# PCB_PI.net
KiCad netlist of a schematic drawn in EasyEDA
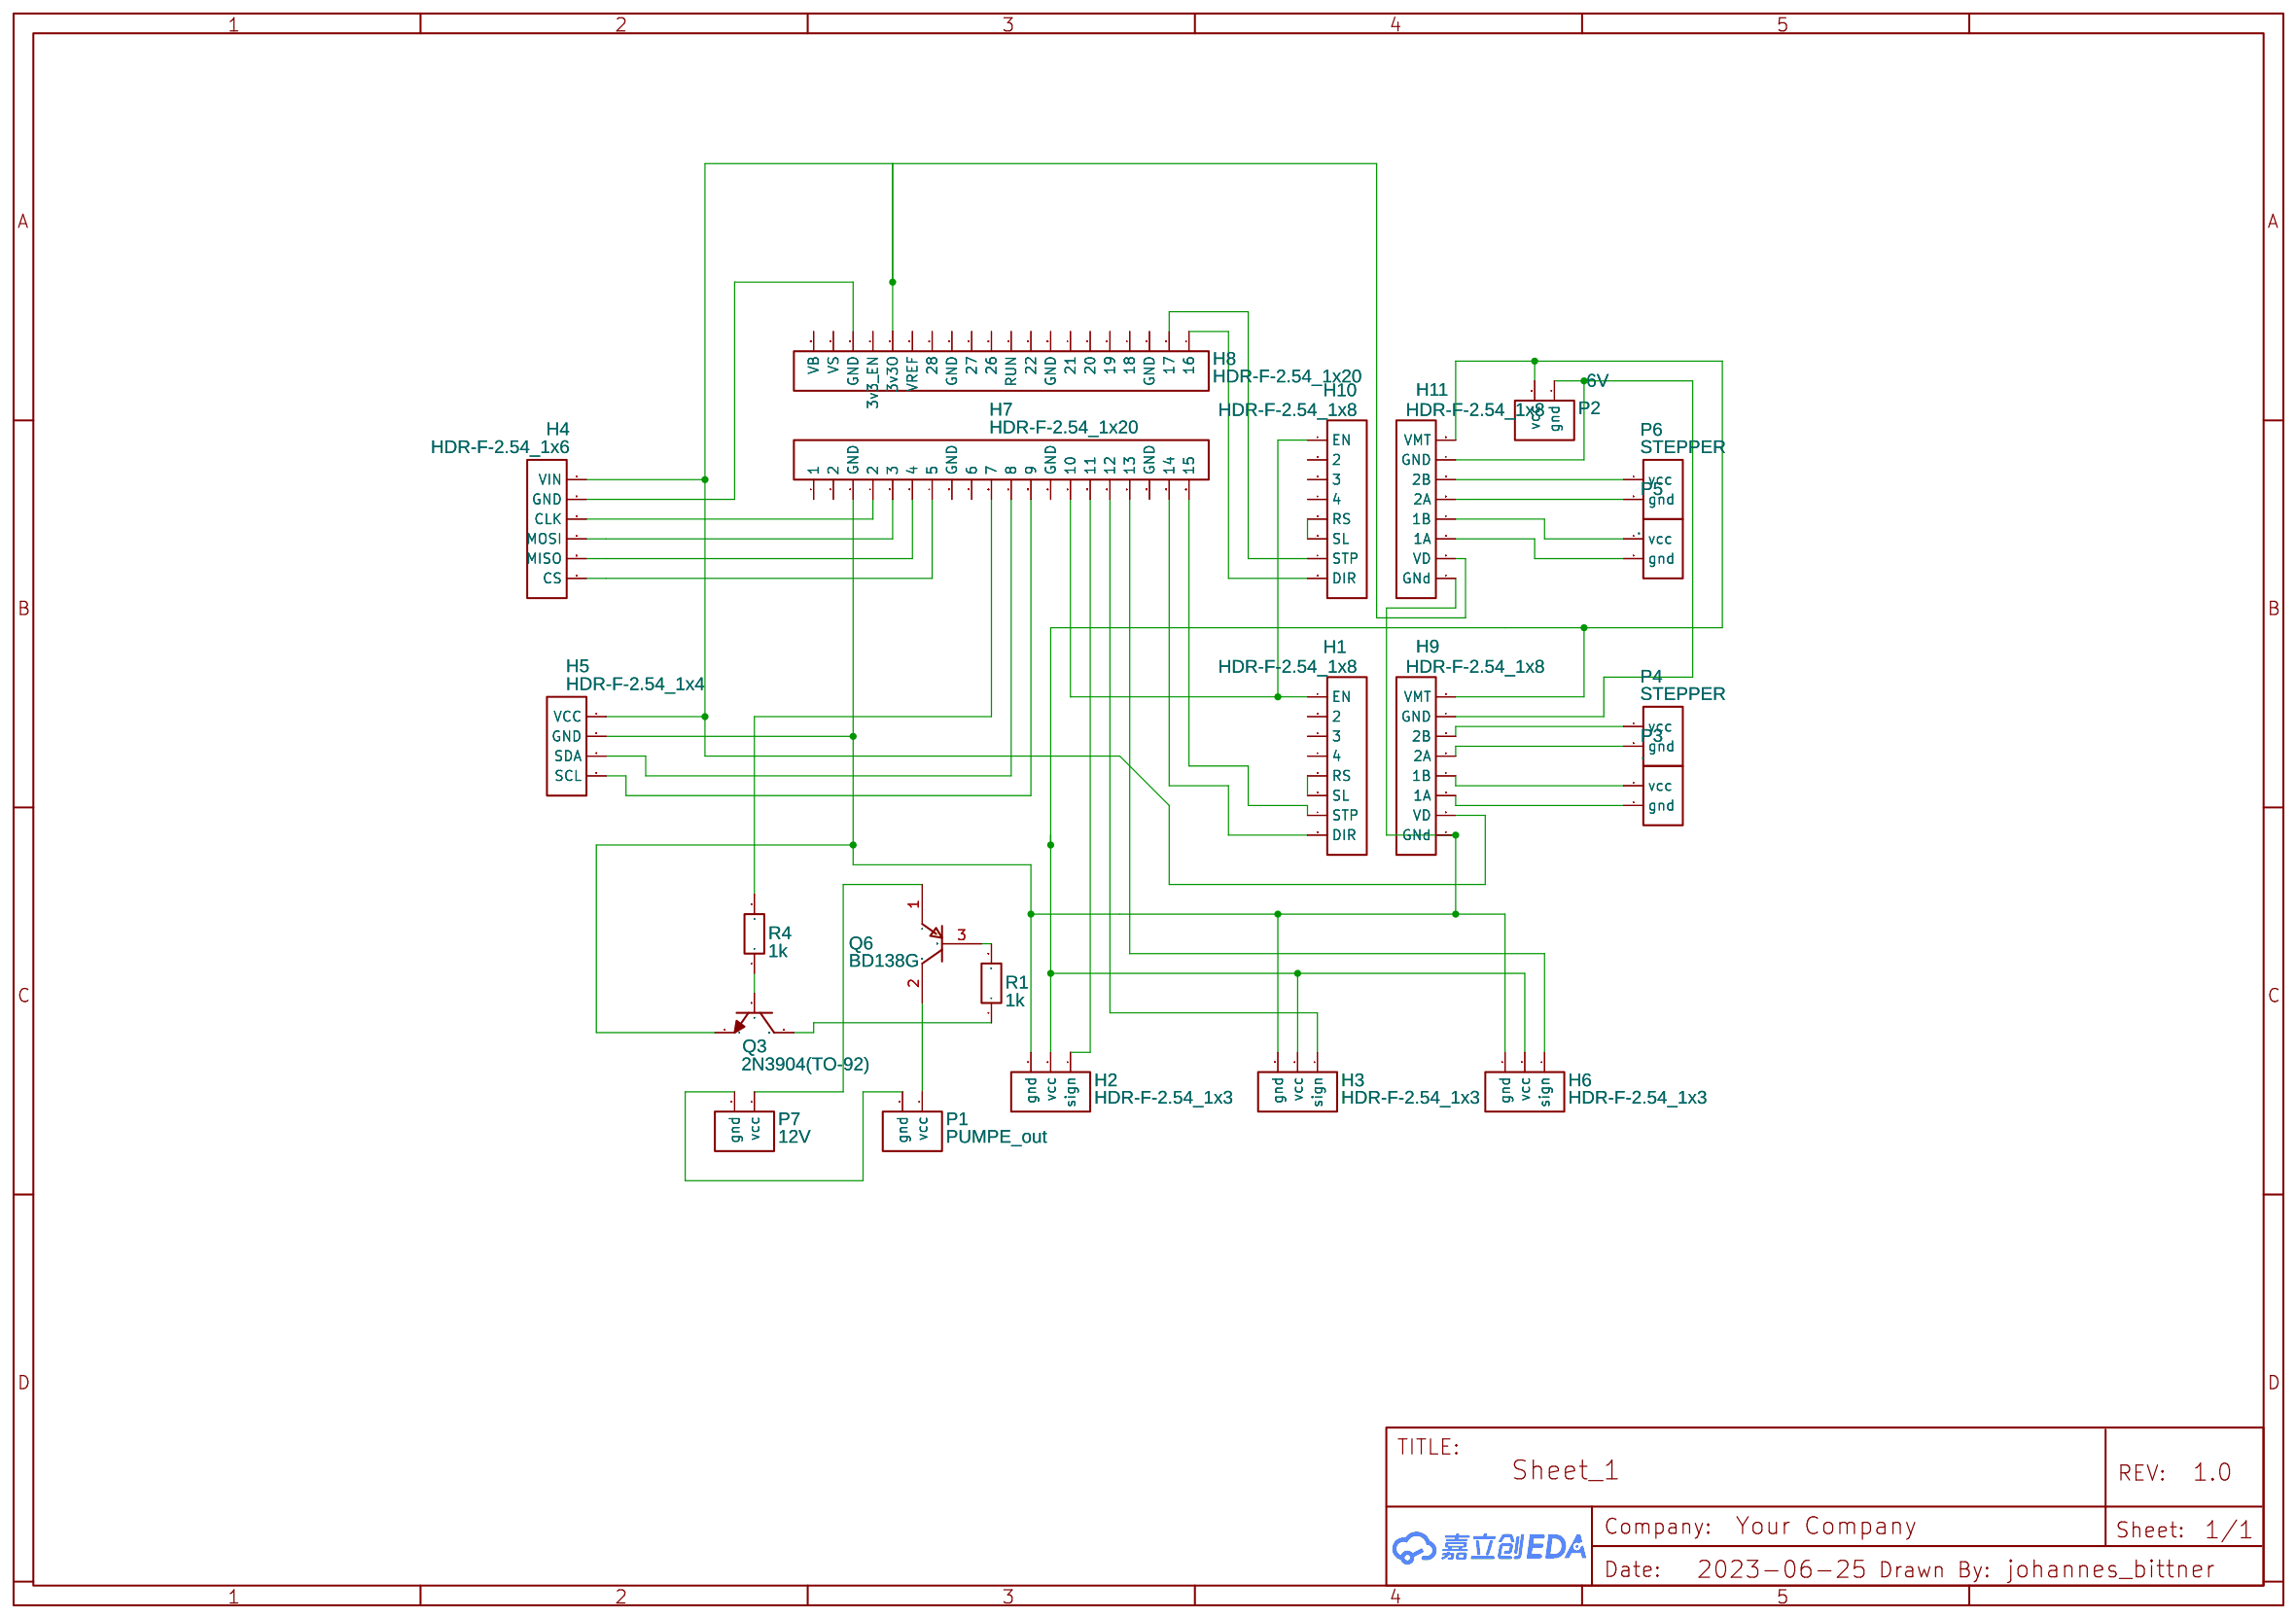
[diagram p0: schematic sheet]

(export (version "E")
  (design (tool "Eeschema 10.0.6"))
  (components
    (comp (ref "H1")
      (value "HDR-F-2.54_1x8")
      (fields (field (name "BOM_Supplier Part") "C225505"))
      (libsource (lib "") (part "HDR-F-2.54_1x8_1"))
    )
    (comp (ref "H2")
      (value "HDR-F-2.54_1x3")
      (fields (field (name "BOM_Supplier Part") "C146690"))
      (libsource (lib "") (part "HDR-F-2.54_1x3"))
    )
    (comp (ref "H3")
      (value "HDR-F-2.54_1x3")
      (fields (field (name "BOM_Supplier Part") "C146690"))
      (libsource (lib "") (part "HDR-F-2.54_1x3"))
    )
    (comp (ref "H4")
      (value "HDR-F-2.54_1x6")
      (fields (field (name "BOM_Supplier Part") "C40877"))
      (libsource (lib "") (part "HDR-F-2.54_1x6"))
    )
    (comp (ref "H5")
      (value "HDR-F-2.54_1x4")
      (fields (field (name "BOM_Supplier Part") "C225501"))
      (libsource (lib "") (part "HDR-F-2.54_1x4"))
    )
    (comp (ref "H6")
      (value "HDR-F-2.54_1x3")
      (fields (field (name "BOM_Supplier Part") "C146690"))
      (libsource (lib "") (part "HDR-F-2.54_1x3"))
    )
    (comp (ref "H7")
      (value "HDR-F-2.54_1x20")
      (fields (field (name "BOM_Supplier Part") "C50984"))
      (libsource (lib "") (part "HDR-F-2.54_1x20"))
    )
    (comp (ref "H8")
      (value "HDR-F-2.54_1x20")
      (fields (field (name "BOM_Supplier Part") "C50984"))
      (libsource (lib "") (part "HDR-F-2.54_1x20_1"))
    )
    (comp (ref "H9")
      (value "HDR-F-2.54_1x8")
      (fields (field (name "BOM_Supplier Part") "C225505"))
      (libsource (lib "") (part "HDR-F-2.54_1x8"))
    )
    (comp (ref "H10")
      (value "HDR-F-2.54_1x8")
      (fields (field (name "BOM_Supplier Part") "C225505"))
      (libsource (lib "") (part "HDR-F-2.54_1x8_1"))
    )
    (comp (ref "H11")
      (value "HDR-F-2.54_1x8")
      (fields (field (name "BOM_Supplier Part") "C225505"))
      (libsource (lib "") (part "HDR-F-2.54_1x8"))
    )
    (comp (ref "P1") (value "PUMPE_out") (libsource (lib "") (part "CONN-TH_2P-P5.00_1")))
    (comp (ref "P2") (value "6V") (libsource (lib "") (part "CONN-TH_2P-P5.00_2")))
    (comp (ref "P3") (value ".") (libsource (lib "") (part "CONN-TH_2P-P5.00")))
    (comp (ref "P4") (value "STEPPER") (libsource (lib "") (part "CONN-TH_2P-P5.00")))
    (comp (ref "P5") (value ".") (libsource (lib "") (part "CONN-TH_2P-P5.00")))
    (comp (ref "P6") (value "STEPPER") (libsource (lib "") (part "CONN-TH_2P-P5.00")))
    (comp (ref "P7") (value "12V") (libsource (lib "") (part "CONN-TH_2P-P5.00_1")))
    (comp (ref "Q3")
      (value "2N3904(TO-92)")
      (fields (field (name "BOM_Manufacturer Part") "2N3904") (field (name "BOM_Supplier Part") "C118538"))
      (libsource (lib "") (part "2N3904(TO-92)"))
    )
    (comp (ref "Q6") (value "BD138G") (libsource (lib "") (part "BD138G")))
    (comp (ref "R1") (value "1k") (libsource (lib "") (part "R_AXIAL-0.5_EU")))
    (comp (ref "R4") (value "1k") (libsource (lib "") (part "R_AXIAL-0.5_EU")))
  )
  (nets
    (net (code "1") (name "Net-(H1-DIR)") (class "Default")
      (node (ref "H1") (pin "8") (pinfunction "DIR_8") (pintype "unspecified"))
      (node (ref "H7") (pin "19") (pinfunction "14_19") (pintype "unspecified"))
    )
    (net (code "2") (name "Net-(H1-EN)") (class "Default")
      (node (ref "H1") (pin "1") (pinfunction "EN_1") (pintype "unspecified"))
      (node (ref "H10") (pin "1") (pinfunction "EN_1") (pintype "unspecified"))
      (node (ref "H7") (pin "14") (pinfunction "10_14") (pintype "unspecified"))
    )
    (net (code "3") (name "Net-(H1-RS)") (class "Default")
      (node (ref "H1") (pin "5") (pinfunction "RS_5") (pintype "unspecified"))
      (node (ref "H1") (pin "6") (pinfunction "SL_6") (pintype "unspecified"))
    )
    (net (code "4") (name "Net-(H1-STP)") (class "Default")
      (node (ref "H1") (pin "7") (pinfunction "STP_7") (pintype "unspecified"))
      (node (ref "H7") (pin "20") (pinfunction "15_20") (pintype "unspecified"))
    )
    (net (code "5") (name "Net-(H2-sign)") (class "Default")
      (node (ref "H2") (pin "1") (pinfunction "sign_1") (pintype "input"))
      (node (ref "H7") (pin "15") (pinfunction "11_15") (pintype "unspecified"))
    )
    (net (code "6") (name "Net-(H3-sign)") (class "Default")
      (node (ref "H3") (pin "1") (pinfunction "sign_1") (pintype "input"))
      (node (ref "H7") (pin "16") (pinfunction "12_16") (pintype "unspecified"))
    )
    (net (code "7") (name "Net-(H4-CLK)") (class "Default")
      (node (ref "H4") (pin "3") (pinfunction "CLK_3") (pintype "input"))
      (node (ref "H7") (pin "4") (pinfunction "2_4") (pintype "unspecified"))
    )
    (net (code "8") (name "Net-(H4-CS)") (class "Default")
      (node (ref "H4") (pin "6") (pinfunction "CS_6") (pintype "input"))
      (node (ref "H7") (pin "7") (pinfunction "5_7") (pintype "unspecified"))
    )
    (net (code "9") (name "Net-(H4-GND)") (class "Default")
      (node (ref "H4") (pin "2") (pinfunction "GND_2") (pintype "input"))
      (node (ref "H8") (pin "18") (pinfunction "GND_18") (pintype "unspecified"))
    )
    (net (code "10") (name "Net-(H4-MISO)") (class "Default")
      (node (ref "H4") (pin "5") (pinfunction "MISO_5") (pintype "input"))
      (node (ref "H7") (pin "6") (pinfunction "4_6") (pintype "unspecified"))
    )
    (net (code "11") (name "Net-(H4-MOSI)") (class "Default")
      (node (ref "H4") (pin "4") (pinfunction "MOSI_4") (pintype "input"))
      (node (ref "H7") (pin "5") (pinfunction "3_5") (pintype "unspecified"))
    )
    (net (code "12") (name "Net-(H5-SCL)") (class "Default")
      (node (ref "H5") (pin "1") (pinfunction "SCL_1") (pintype "unspecified"))
      (node (ref "H7") (pin "12") (pinfunction "9_12") (pintype "unspecified"))
    )
    (net (code "13") (name "Net-(H5-SDA)") (class "Default")
      (node (ref "H5") (pin "2") (pinfunction "SDA_2") (pintype "unspecified"))
      (node (ref "H7") (pin "11") (pinfunction "8_11") (pintype "unspecified"))
    )
    (net (code "14") (name "Net-(H6-sign)") (class "Default")
      (node (ref "H6") (pin "1") (pinfunction "sign_1") (pintype "input"))
      (node (ref "H7") (pin "17") (pinfunction "13_17") (pintype "unspecified"))
    )
    (net (code "15") (name "Net-(H7-7)") (class "Default")
      (node (ref "H7") (pin "10") (pinfunction "7_10") (pintype "unspecified"))
      (node (ref "R4") (pin "2") (pinfunction "2_2") (pintype "unspecified"))
    )
    (net (code "16") (name "Net-(H9-1A)") (class "Default")
      (node (ref "H9") (pin "3") (pinfunction "1A_3") (pintype "unspecified"))
      (node (ref "P3") (pin "2") (pinfunction "gnd_2") (pintype "unspecified"))
    )
    (net (code "17") (name "Net-(H9-1B)") (class "Default")
      (node (ref "H9") (pin "4") (pinfunction "1B_4") (pintype "unspecified"))
      (node (ref "P3") (pin "1") (pinfunction "vcc_1") (pintype "unspecified"))
    )
    (net (code "18") (name "Net-(H9-2A)") (class "Default")
      (node (ref "H9") (pin "5") (pinfunction "2A_5") (pintype "unspecified"))
      (node (ref "P4") (pin "2") (pinfunction "gnd_2") (pintype "unspecified"))
    )
    (net (code "19") (name "Net-(H9-2B)") (class "Default")
      (node (ref "H9") (pin "6") (pinfunction "2B_6") (pintype "unspecified"))
      (node (ref "P4") (pin "1") (pinfunction "vcc_1") (pintype "unspecified"))
    )
    (net (code "20") (name "Net-(H10-DIR)") (class "Default")
      (node (ref "H10") (pin "8") (pinfunction "DIR_8") (pintype "unspecified"))
      (node (ref "H8") (pin "1") (pinfunction "16_1") (pintype "unspecified"))
    )
    (net (code "21") (name "Net-(H10-RS)") (class "Default")
      (node (ref "H10") (pin "5") (pinfunction "RS_5") (pintype "unspecified"))
      (node (ref "H10") (pin "6") (pinfunction "SL_6") (pintype "unspecified"))
    )
    (net (code "22") (name "Net-(H10-STP)") (class "Default")
      (node (ref "H10") (pin "7") (pinfunction "STP_7") (pintype "unspecified"))
      (node (ref "H8") (pin "2") (pinfunction "17_2") (pintype "unspecified"))
    )
    (net (code "23") (name "Net-(H11-1A)") (class "Default")
      (node (ref "H11") (pin "3") (pinfunction "1A_3") (pintype "unspecified"))
      (node (ref "P5") (pin "2") (pinfunction "gnd_2") (pintype "unspecified"))
    )
    (net (code "24") (name "Net-(H11-1B)") (class "Default")
      (node (ref "H11") (pin "4") (pinfunction "1B_4") (pintype "unspecified"))
      (node (ref "P5") (pin "1") (pinfunction "vcc_1") (pintype "unspecified"))
    )
    (net (code "25") (name "Net-(H11-2A)") (class "Default")
      (node (ref "H11") (pin "5") (pinfunction "2A_5") (pintype "unspecified"))
      (node (ref "P6") (pin "2") (pinfunction "gnd_2") (pintype "unspecified"))
    )
    (net (code "26") (name "Net-(H11-2B)") (class "Default")
      (node (ref "H11") (pin "6") (pinfunction "2B_6") (pintype "unspecified"))
      (node (ref "P6") (pin "1") (pinfunction "vcc_1") (pintype "unspecified"))
    )
    (net (code "27") (name "Net-(H11-GND)") (class "Default")
      (node (ref "H11") (pin "7") (pinfunction "GND_7") (pintype "unspecified"))
      (node (ref "H9") (pin "7") (pinfunction "GND_7") (pintype "unspecified"))
      (node (ref "P2") (pin "1") (pinfunction "gnd_1") (pintype "unspecified"))
    )
    (net (code "28") (name "Net-(H11-GNd)") (class "Default")
      (node (ref "H11") (pin "1") (pinfunction "GNd_1") (pintype "unspecified"))
      (node (ref "H2") (pin "3") (pinfunction "gnd_3") (pintype "input"))
      (node (ref "H3") (pin "3") (pinfunction "gnd_3") (pintype "input"))
      (node (ref "H5") (pin "3") (pinfunction "GND_3") (pintype "unspecified"))
      (node (ref "H6") (pin "3") (pinfunction "gnd_3") (pintype "input"))
      (node (ref "H7") (pin "3") (pinfunction "GND_3") (pintype "unspecified"))
      (node (ref "H9") (pin "1") (pinfunction "GNd_1") (pintype "unspecified"))
      (node (ref "Q3") (pin "1") (pinfunction "E_1") (pintype "unspecified"))
    )
    (net (code "29") (name "Net-(H11-VD)") (class "Default")
      (node (ref "H11") (pin "2") (pinfunction "VD_2") (pintype "unspecified"))
      (node (ref "H4") (pin "1") (pinfunction "VIN_1") (pintype "input"))
      (node (ref "H5") (pin "4") (pinfunction "VCC_4") (pintype "unspecified"))
      (node (ref "H8") (pin "16") (pinfunction "3v3O_16") (pintype "unspecified"))
      (node (ref "H9") (pin "2") (pinfunction "VD_2") (pintype "unspecified"))
    )
    (net (code "30") (name "Net-(H11-VMT)") (class "Default")
      (node (ref "H11") (pin "8") (pinfunction "VMT_8") (pintype "unspecified"))
      (node (ref "H2") (pin "2") (pinfunction "vcc_2") (pintype "input"))
      (node (ref "H3") (pin "2") (pinfunction "vcc_2") (pintype "input"))
      (node (ref "H6") (pin "2") (pinfunction "vcc_2") (pintype "input"))
      (node (ref "H9") (pin "8") (pinfunction "VMT_8") (pintype "unspecified"))
      (node (ref "P2") (pin "2") (pinfunction "vcc_2") (pintype "unspecified"))
    )
    (net (code "31") (name "Net-(P1-gnd)") (class "Default")
      (node (ref "P1") (pin "2") (pinfunction "gnd_2") (pintype "unspecified"))
      (node (ref "P7") (pin "2") (pinfunction "gnd_2") (pintype "unspecified"))
    )
    (net (code "32") (name "Net-(P1-vcc)") (class "Default")
      (node (ref "P1") (pin "1") (pinfunction "vcc_1") (pintype "unspecified"))
      (node (ref "Q6") (pin "2") (pinfunction "C_2") (pintype "unspecified"))
    )
    (net (code "33") (name "Net-(P7-vcc)") (class "Default")
      (node (ref "P7") (pin "1") (pinfunction "vcc_1") (pintype "unspecified"))
      (node (ref "Q6") (pin "1") (pinfunction "E_1") (pintype "unspecified"))
    )
    (net (code "34") (name "Net-(Q3-B)") (class "Default")
      (node (ref "Q3") (pin "2") (pinfunction "B_2") (pintype "unspecified"))
      (node (ref "R4") (pin "1") (pinfunction "1_1") (pintype "unspecified"))
    )
    (net (code "35") (name "Net-(Q3-C)") (class "Default")
      (node (ref "Q3") (pin "3") (pinfunction "C_3") (pintype "unspecified"))
      (node (ref "R1") (pin "1") (pinfunction "1_1") (pintype "unspecified"))
    )
    (net (code "36") (name "Net-(Q6-B)") (class "Default")
      (node (ref "Q6") (pin "3") (pinfunction "B_3") (pintype "unspecified"))
      (node (ref "R1") (pin "2") (pinfunction "2_2") (pintype "unspecified"))
    )
    (net (code "37") (name "unconnected-(H1-Pad2)") (class "Default")
      (node (ref "H1") (pin "2") (pinfunction "2_2") (pintype "unspecified"))
    )
    (net (code "38") (name "unconnected-(H1-Pad3)") (class "Default")
      (node (ref "H1") (pin "3") (pinfunction "3_3") (pintype "unspecified"))
    )
    (net (code "39") (name "unconnected-(H1-Pad4)") (class "Default")
      (node (ref "H1") (pin "4") (pinfunction "4_4") (pintype "unspecified"))
    )
    (net (code "40") (name "unconnected-(H7-6-Pad9)") (class "Default")
      (node (ref "H7") (pin "9") (pinfunction "6_9") (pintype "unspecified"))
    )
    (net (code "41") (name "unconnected-(H7-GND-Pad8)") (class "Default")
      (node (ref "H7") (pin "8") (pinfunction "GND_8") (pintype "unspecified"))
    )
    (net (code "42") (name "unconnected-(H7-GND-Pad13)") (class "Default")
      (node (ref "H7") (pin "13") (pinfunction "GND_13") (pintype "unspecified"))
    )
    (net (code "43") (name "unconnected-(H7-GND-Pad18)") (class "Default")
      (node (ref "H7") (pin "18") (pinfunction "GND_18") (pintype "unspecified"))
    )
    (net (code "44") (name "unconnected-(H7-Pad1)") (class "Default")
      (node (ref "H7") (pin "1") (pinfunction "1_1") (pintype "unspecified"))
    )
    (net (code "45") (name "unconnected-(H7-Pad2)") (class "Default")
      (node (ref "H7") (pin "2") (pinfunction "2_2") (pintype "unspecified"))
    )
    (net (code "46") (name "unconnected-(H8-3v3_EN-Pad17)") (class "Default")
      (node (ref "H8") (pin "17") (pinfunction "3v3_EN_17") (pintype "unspecified"))
    )
    (net (code "47") (name "unconnected-(H8-18-Pad4)") (class "Default")
      (node (ref "H8") (pin "4") (pinfunction "18_4") (pintype "unspecified"))
    )
    (net (code "48") (name "unconnected-(H8-19-Pad5)") (class "Default")
      (node (ref "H8") (pin "5") (pinfunction "19_5") (pintype "unspecified"))
    )
    (net (code "49") (name "unconnected-(H8-20-Pad6)") (class "Default")
      (node (ref "H8") (pin "6") (pinfunction "20_6") (pintype "unspecified"))
    )
    (net (code "50") (name "unconnected-(H8-21-Pad7)") (class "Default")
      (node (ref "H8") (pin "7") (pinfunction "21_7") (pintype "unspecified"))
    )
    (net (code "51") (name "unconnected-(H8-22-Pad9)") (class "Default")
      (node (ref "H8") (pin "9") (pinfunction "22_9") (pintype "unspecified"))
    )
    (net (code "52") (name "unconnected-(H8-26-Pad11)") (class "Default")
      (node (ref "H8") (pin "11") (pinfunction "26_11") (pintype "unspecified"))
    )
    (net (code "53") (name "unconnected-(H8-27-Pad12)") (class "Default")
      (node (ref "H8") (pin "12") (pinfunction "27_12") (pintype "unspecified"))
    )
    (net (code "54") (name "unconnected-(H8-28-Pad14)") (class "Default")
      (node (ref "H8") (pin "14") (pinfunction "28_14") (pintype "unspecified"))
    )
    (net (code "55") (name "unconnected-(H8-GND-Pad3)") (class "Default")
      (node (ref "H8") (pin "3") (pinfunction "GND_3") (pintype "unspecified"))
    )
    (net (code "56") (name "unconnected-(H8-GND-Pad8)") (class "Default")
      (node (ref "H8") (pin "8") (pinfunction "GND_8") (pintype "unspecified"))
    )
    (net (code "57") (name "unconnected-(H8-GND-Pad13)") (class "Default")
      (node (ref "H8") (pin "13") (pinfunction "GND_13") (pintype "unspecified"))
    )
    (net (code "58") (name "unconnected-(H8-RUN-Pad10)") (class "Default")
      (node (ref "H8") (pin "10") (pinfunction "RUN_10") (pintype "unspecified"))
    )
    (net (code "59") (name "unconnected-(H8-VB-Pad20)") (class "Default")
      (node (ref "H8") (pin "20") (pinfunction "VB_20") (pintype "unspecified"))
    )
    (net (code "60") (name "unconnected-(H8-VREF-Pad15)") (class "Default")
      (node (ref "H8") (pin "15") (pinfunction "VREF_15") (pintype "unspecified"))
    )
    (net (code "61") (name "unconnected-(H8-VS-Pad19)") (class "Default")
      (node (ref "H8") (pin "19") (pinfunction "VS_19") (pintype "unspecified"))
    )
    (net (code "62") (name "unconnected-(H10-Pad2)") (class "Default")
      (node (ref "H10") (pin "2") (pinfunction "2_2") (pintype "unspecified"))
    )
    (net (code "63") (name "unconnected-(H10-Pad3)") (class "Default")
      (node (ref "H10") (pin "3") (pinfunction "3_3") (pintype "unspecified"))
    )
    (net (code "64") (name "unconnected-(H10-Pad4)") (class "Default")
      (node (ref "H10") (pin "4") (pinfunction "4_4") (pintype "unspecified"))
    )
  )
)
